# ezlpc.net
KiCad netlist of a schematic drawn in EAGLE
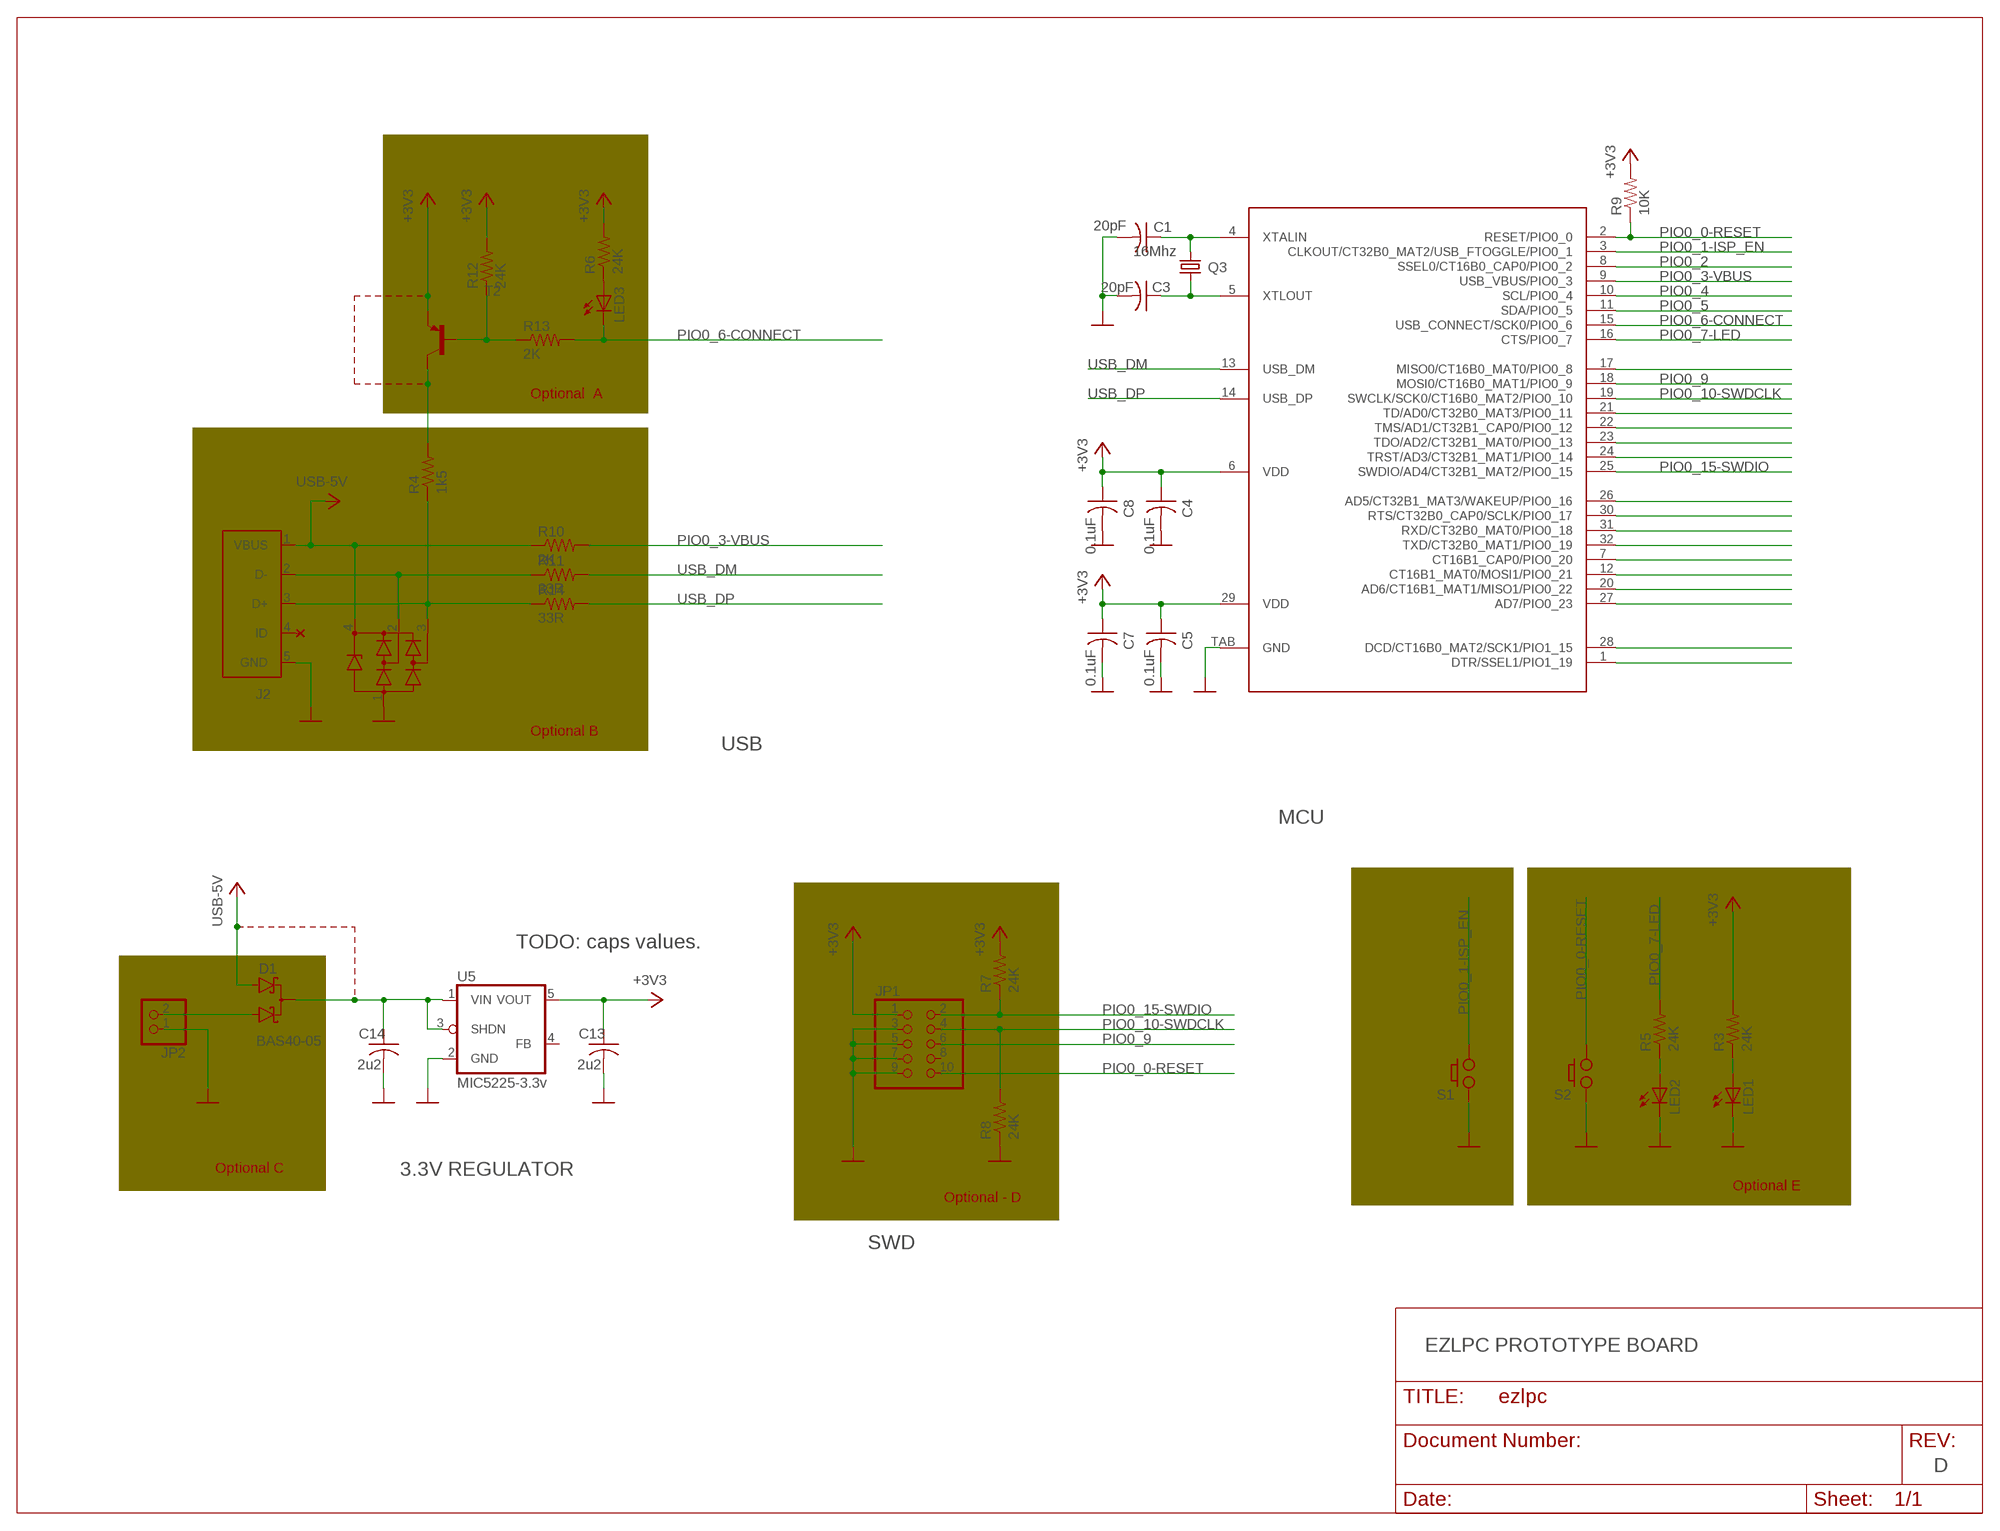
[diagram p0: schematic, sheet 1]

(export (version "E")
  (design (tool "Eeschema 10.0.6"))
  (components
    (comp (ref "C1")
      (value "20pF")
      (footprint "eagle-import:C0603")
      (libsource (lib "eagle-import") (part "CAP-C0603"))
    )
    (comp (ref "C3")
      (value "20pF")
      (footprint "eagle-import:C0603")
      (libsource (lib "eagle-import") (part "CAP-C0603"))
    )
    (comp (ref "C4")
      (value "0.1uF")
      (footprint "eagle-import:C0603")
      (libsource (lib "eagle-import") (part "CAP-C0603"))
    )
    (comp (ref "C5")
      (value "0.1uF")
      (footprint "eagle-import:C0603")
      (libsource (lib "eagle-import") (part "CAP-C0603"))
    )
    (comp (ref "C7")
      (value "0.1uF")
      (footprint "eagle-import:C0603")
      (libsource (lib "eagle-import") (part "CAP-C0603"))
    )
    (comp (ref "C8")
      (value "0.1uF")
      (footprint "eagle-import:C0603")
      (libsource (lib "eagle-import") (part "CAP-C0603"))
    )
    (comp (ref "C13")
      (value "2u2")
      (footprint "eagle-import:C0603")
      (libsource (lib "eagle-import") (part "CAP-C0603"))
    )
    (comp (ref "C14")
      (value "2u2")
      (footprint "eagle-import:C0603")
      (libsource (lib "eagle-import") (part "CAP-C0603"))
    )
    (comp (ref "D1")
      (value "BAS40-05")
      (footprint "eagle-import:SOT23")
      (libsource (lib "eagle-import") (part "BAS40-05"))
    )
    (comp (ref "J2")
      (value "USB")
      (footprint "eagle-import:USB-MICRO-ZX62RD-AB-5P8")
      (libsource (lib "eagle-import") (part "USB"))
    )
    (comp (ref "JP1")
      (value "SWD-HEADER")
      (footprint "eagle-import:SWD-HEADER")
      (libsource (lib "eagle-import") (part "SWD-HEADER"))
    )
    (comp (ref "JP2")
      (value "PINHD-1X2")
      (footprint "eagle-import:1X02")
      (libsource (lib "eagle-import") (part "PINHD-1X2"))
    )
    (comp (ref "LED1")
      (value "LEDCHIP-LED0603")
      (footprint "eagle-import:CHIP-LED0603")
      (libsource (lib "eagle-import") (part "LEDCHIP-LED0603"))
    )
    (comp (ref "LED2")
      (value "LEDCHIP-LED0603")
      (footprint "eagle-import:CHIP-LED0603")
      (libsource (lib "eagle-import") (part "LEDCHIP-LED0603"))
    )
    (comp (ref "LED3")
      (value "LEDCHIP-LED0603")
      (footprint "eagle-import:CHIP-LED0603")
      (libsource (lib "eagle-import") (part "LEDCHIP-LED0603"))
    )
    (comp (ref "Q3")
      (value "16Mhz")
      (footprint "eagle-import:CRYSTAL-CTS406")
      (libsource (lib "eagle-import") (part "CRYSTALCTS406"))
    )
    (comp (ref "R3")
      (value "24K")
      (footprint "eagle-import:R0402")
      (libsource (lib "eagle-import") (part "R-US_R0402"))
    )
    (comp (ref "R4")
      (value "1k5")
      (footprint "eagle-import:R0402")
      (libsource (lib "eagle-import") (part "R-US_R0402"))
    )
    (comp (ref "R5")
      (value "24K")
      (footprint "eagle-import:R0402")
      (libsource (lib "eagle-import") (part "R-US_R0402"))
    )
    (comp (ref "R6")
      (value "24K")
      (footprint "eagle-import:R0402")
      (libsource (lib "eagle-import") (part "R-US_R0402"))
    )
    (comp (ref "R7")
      (value "24K")
      (footprint "eagle-import:R0402")
      (libsource (lib "eagle-import") (part "R-US_R0402"))
    )
    (comp (ref "R8")
      (value "24K")
      (footprint "eagle-import:R0402")
      (libsource (lib "eagle-import") (part "R-US_R0402"))
    )
    (comp (ref "R9")
      (value "10K")
      (footprint "eagle-import:R0402")
      (libsource (lib "eagle-import") (part "R-US_R0402"))
    )
    (comp (ref "R10")
      (value "2K")
      (footprint "eagle-import:R0402")
      (libsource (lib "eagle-import") (part "R-US_R0402"))
    )
    (comp (ref "R11")
      (value "33R")
      (footprint "eagle-import:R0402")
      (libsource (lib "eagle-import") (part "R-US_R0402"))
    )
    (comp (ref "R12")
      (value "24K")
      (footprint "eagle-import:R0402")
      (libsource (lib "eagle-import") (part "R-US_R0402"))
    )
    (comp (ref "R13")
      (value "2K")
      (footprint "eagle-import:R0402")
      (libsource (lib "eagle-import") (part "R-US_R0402"))
    )
    (comp (ref "R14")
      (value "33R")
      (footprint "eagle-import:R0402")
      (libsource (lib "eagle-import") (part "R-US_R0402"))
    )
    (comp (ref "S1")
      (value "PUSH_BUTTON")
      (footprint "eagle-import:PUSH_BUTTON")
      (libsource (lib "eagle-import") (part "PUSH_BUTTON"))
    )
    (comp (ref "S2")
      (value "PUSH_BUTTON")
      (footprint "eagle-import:PUSH_BUTTON")
      (libsource (lib "eagle-import") (part "PUSH_BUTTON"))
    )
    (comp (ref "T2")
      (value "BC857B-PNP-SOT23-BEC")
      (footprint "eagle-import:SOT23-BEC")
      (libsource (lib "eagle-import") (part "-PNP-SOT23-BECBC857B"))
    )
    (comp (ref "U$5")
      (value "PRTR5VOU2X")
      (footprint "eagle-import:SOT143B")
      (libsource (lib "eagle-import") (part "PRTR5VOU2X"))
    )
    (comp (ref "U4")
      (value "LPC11U35FHN33/501")
      (footprint "eagle-import:HVQFN33-5MM")
      (libsource (lib "eagle-import") (part "LPC11U35FHN33/501"))
    )
    (comp (ref "U5")
      (value "MIC5225-3.3v")
      (footprint "eagle-import:SOT25")
      (libsource (lib "eagle-import") (part "TC1015"))
    )
  )
  (nets
    (net (code "1") (name "+3V3") (class "Default")
      (node (ref "C13") (pin "1") (pinfunction "1_1") (pintype "passive"))
      (node (ref "C4") (pin "1") (pinfunction "1_1") (pintype "passive"))
      (node (ref "C5") (pin "1") (pinfunction "1_1") (pintype "passive"))
      (node (ref "C7") (pin "1") (pinfunction "1_1") (pintype "passive"))
      (node (ref "C8") (pin "1") (pinfunction "1_1") (pintype "passive"))
      (node (ref "JP1") (pin "1") (pinfunction "1_1") (pintype "passive"))
      (node (ref "R12") (pin "2") (pinfunction "2_2") (pintype "passive"))
      (node (ref "R3") (pin "2") (pinfunction "2_2") (pintype "passive"))
      (node (ref "R6") (pin "2") (pinfunction "2_2") (pintype "passive"))
      (node (ref "R7") (pin "2") (pinfunction "2_2") (pintype "passive"))
      (node (ref "R9") (pin "2") (pinfunction "2_2") (pintype "passive"))
      (node (ref "T2") (pin "E") (pinfunction "E_E") (pintype "passive"))
      (node (ref "U4") (pin "29") (pinfunction "VDD_29") (pintype "bidirectional"))
      (node (ref "U4") (pin "6") (pinfunction "VDD_6") (pintype "bidirectional"))
      (node (ref "U5") (pin "5") (pinfunction "VOUT_5") (pintype "power_in"))
    )
    (net (code "2") (name "/PIO0_0-RESET") (class "Default")
      (node (ref "JP1") (pin "10") (pinfunction "10_10") (pintype "passive"))
      (node (ref "R9") (pin "1") (pinfunction "1_1") (pintype "passive"))
      (node (ref "S2") (pin "B2") (pinfunction "2_B2") (pintype "passive"))
      (node (ref "U4") (pin "2") (pinfunction "RESET/PIO0_0_2") (pintype "bidirectional"))
    )
    (net (code "3") (name "/PIO0_1-ISP_EN") (class "Default")
      (node (ref "S1") (pin "B2") (pinfunction "2_B2") (pintype "passive"))
      (node (ref "U4") (pin "3") (pinfunction "CLKOUT/CT32B0_MAT2/USB_FTOGGLE/PIO0_1_3") (pintype "bidirectional"))
    )
    (net (code "4") (name "/PIO0_2") (class "Default")
      (node (ref "U4") (pin "8") (pinfunction "SSEL0/CT16B0_CAP0/PIO0_2_8") (pintype "bidirectional"))
    )
    (net (code "5") (name "/PIO0_3-VBUS") (class "Default")
      (node (ref "R10") (pin "2") (pinfunction "2_2") (pintype "passive"))
      (node (ref "U4") (pin "9") (pinfunction "USB_VBUS/PIO0_3_9") (pintype "bidirectional"))
    )
    (net (code "6") (name "/PIO0_4") (class "Default")
      (node (ref "U4") (pin "10") (pinfunction "SCL/PIO0_4_10") (pintype "bidirectional"))
    )
    (net (code "7") (name "/PIO0_5") (class "Default")
      (node (ref "U4") (pin "11") (pinfunction "SDA/PIO0_5_11") (pintype "bidirectional"))
    )
    (net (code "8") (name "/PIO0_6-CONNECT") (class "Default")
      (node (ref "LED3") (pin "C") (pinfunction "C_C") (pintype "passive"))
      (node (ref "R13") (pin "2") (pinfunction "2_2") (pintype "passive"))
      (node (ref "U4") (pin "15") (pinfunction "USB_CONNECT/SCK0/PIO0_6_15") (pintype "bidirectional"))
    )
    (net (code "9") (name "/PIO0_7-LED") (class "Default")
      (node (ref "R5") (pin "2") (pinfunction "2_2") (pintype "passive"))
      (node (ref "U4") (pin "16") (pinfunction "CTS/PIO0_7_16") (pintype "bidirectional"))
    )
    (net (code "10") (name "/PIO0_9") (class "Default")
      (node (ref "JP1") (pin "6") (pinfunction "6_6") (pintype "passive"))
      (node (ref "U4") (pin "18") (pinfunction "MOSI0/CT16B0_MAT1/PIO0_9_18") (pintype "bidirectional"))
    )
    (net (code "11") (name "/PIO0_10-SWDCLK") (class "Default")
      (node (ref "JP1") (pin "4") (pinfunction "4_4") (pintype "passive"))
      (node (ref "R8") (pin "2") (pinfunction "2_2") (pintype "passive"))
      (node (ref "U4") (pin "19") (pinfunction "SWCLK/SCK0/CT16B0_MAT2/PIO0_10_19") (pintype "bidirectional"))
    )
    (net (code "12") (name "/PIO0_15-SWDIO") (class "Default")
      (node (ref "JP1") (pin "2") (pinfunction "2_2") (pintype "passive"))
      (node (ref "R7") (pin "1") (pinfunction "1_1") (pintype "passive"))
      (node (ref "U4") (pin "25") (pinfunction "SWDIO/AD4/CT32B1_MAT2/PIO0_15_25") (pintype "bidirectional"))
    )
    (net (code "13") (name "/USB_DM") (class "Default")
      (node (ref "R11") (pin "2") (pinfunction "2_2") (pintype "passive"))
      (node (ref "U4") (pin "13") (pinfunction "USB_DM_13") (pintype "bidirectional"))
    )
    (net (code "14") (name "/USB_DP") (class "Default")
      (node (ref "R14") (pin "2") (pinfunction "2_2") (pintype "passive"))
      (node (ref "U4") (pin "14") (pinfunction "USB_DP_14") (pintype "bidirectional"))
    )
    (net (code "15") (name "GND") (class "Default")
      (node (ref "C1") (pin "2") (pinfunction "2_2") (pintype "passive"))
      (node (ref "C13") (pin "2") (pinfunction "2_2") (pintype "passive"))
      (node (ref "C14") (pin "2") (pinfunction "2_2") (pintype "passive"))
      (node (ref "C3") (pin "2") (pinfunction "2_2") (pintype "passive"))
      (node (ref "C4") (pin "2") (pinfunction "2_2") (pintype "passive"))
      (node (ref "C5") (pin "2") (pinfunction "2_2") (pintype "passive"))
      (node (ref "C7") (pin "2") (pinfunction "2_2") (pintype "passive"))
      (node (ref "C8") (pin "2") (pinfunction "2_2") (pintype "passive"))
      (node (ref "J2") (pin "5") (pinfunction "GND_5") (pintype "bidirectional"))
      (node (ref "JP1") (pin "3") (pinfunction "3_3") (pintype "passive"))
      (node (ref "JP1") (pin "5") (pinfunction "5_5") (pintype "passive"))
      (node (ref "JP1") (pin "7") (pinfunction "7_7") (pintype "passive"))
      (node (ref "JP1") (pin "9") (pinfunction "9_9") (pintype "passive"))
      (node (ref "JP2") (pin "1") (pinfunction "1_1") (pintype "passive"))
      (node (ref "LED1") (pin "C") (pinfunction "C_C") (pintype "passive"))
      (node (ref "LED2") (pin "C") (pinfunction "C_C") (pintype "passive"))
      (node (ref "R8") (pin "1") (pinfunction "1_1") (pintype "passive"))
      (node (ref "S1") (pin "A1") (pinfunction "1_A1") (pintype "passive"))
      (node (ref "S2") (pin "A1") (pinfunction "1_A1") (pintype "passive"))
      (node (ref "U$5") (pin "1") (pinfunction "GND_1") (pintype "passive"))
      (node (ref "U4") (pin "TAB") (pinfunction "GND_TAB") (pintype "bidirectional"))
      (node (ref "U5") (pin "2") (pinfunction "GND_2") (pintype "power_in"))
    )
    (net (code "16") (name "Net-(D1-A1)") (class "Default")
      (node (ref "D1") (pin "1") (pinfunction "A1_1") (pintype "passive"))
      (node (ref "JP2") (pin "2") (pinfunction "2_2") (pintype "passive"))
    )
    (net (code "17") (name "Net-(D1-C)") (class "Default")
      (node (ref "C14") (pin "1") (pinfunction "1_1") (pintype "passive"))
      (node (ref "D1") (pin "3") (pinfunction "C_3") (pintype "passive"))
      (node (ref "U5") (pin "1") (pinfunction "VIN_1") (pintype "power_in"))
      (node (ref "U5") (pin "3") (pinfunction "SHDN_3") (pintype "input"))
    )
    (net (code "18") (name "Net-(J2-D+)") (class "Default")
      (node (ref "J2") (pin "2") (pinfunction "D-_2") (pintype "bidirectional"))
      (node (ref "J2") (pin "3") (pinfunction "D+_3") (pintype "bidirectional"))
      (node (ref "R11") (pin "1") (pinfunction "1_1") (pintype "passive"))
      (node (ref "R14") (pin "1") (pinfunction "1_1") (pintype "passive"))
      (node (ref "R4") (pin "1") (pinfunction "1_1") (pintype "passive"))
      (node (ref "U$5") (pin "2") (pinfunction "IO1_2") (pintype "passive"))
      (node (ref "U$5") (pin "3") (pinfunction "IO2_3") (pintype "passive"))
    )
    (net (code "19") (name "Net-(LED1-PadA)") (class "Default")
      (node (ref "LED1") (pin "A") (pinfunction "A_A") (pintype "passive"))
      (node (ref "R3") (pin "1") (pinfunction "1_1") (pintype "passive"))
    )
    (net (code "20") (name "Net-(LED2-PadA)") (class "Default")
      (node (ref "LED2") (pin "A") (pinfunction "A_A") (pintype "passive"))
      (node (ref "R5") (pin "1") (pinfunction "1_1") (pintype "passive"))
    )
    (net (code "21") (name "Net-(LED3-PadA)") (class "Default")
      (node (ref "LED3") (pin "A") (pinfunction "A_A") (pintype "passive"))
      (node (ref "R6") (pin "1") (pinfunction "1_1") (pintype "passive"))
    )
    (net (code "22") (name "Net-(Q3-2)") (class "Default")
      (node (ref "C3") (pin "1") (pinfunction "1_1") (pintype "passive"))
      (node (ref "Q3") (pin "3") (pinfunction "2_3") (pintype "passive"))
      (node (ref "U4") (pin "5") (pinfunction "XTLOUT_5") (pintype "bidirectional"))
    )
    (net (code "23") (name "Net-(R4-Pad2)") (class "Default")
      (node (ref "R4") (pin "2") (pinfunction "2_2") (pintype "passive"))
      (node (ref "T2") (pin "C") (pinfunction "C_C") (pintype "passive"))
    )
    (net (code "24") (name "Net-(R12-Pad1)") (class "Default")
      (node (ref "R12") (pin "1") (pinfunction "1_1") (pintype "passive"))
      (node (ref "R13") (pin "1") (pinfunction "1_1") (pintype "passive"))
      (node (ref "T2") (pin "B") (pinfunction "B_B") (pintype "passive"))
    )
    (net (code "25") (name "Net-(U4-XTALIN)") (class "Default")
      (node (ref "C1") (pin "1") (pinfunction "1_1") (pintype "passive"))
      (node (ref "Q3") (pin "1") (pinfunction "1_1") (pintype "passive"))
      (node (ref "U4") (pin "4") (pinfunction "XTALIN_4") (pintype "bidirectional"))
    )
    (net (code "26") (name "USB-5V") (class "Default")
      (node (ref "D1") (pin "2") (pinfunction "A2_2") (pintype "passive"))
      (node (ref "J2") (pin "1") (pinfunction "VBUS_1") (pintype "bidirectional"))
      (node (ref "R10") (pin "1") (pinfunction "1_1") (pintype "passive"))
      (node (ref "U$5") (pin "4") (pinfunction "VCC_4") (pintype "passive"))
    )
    (net (code "27") (name "unconnected-(J2-ID-Pad4)") (class "Default")
      (node (ref "J2") (pin "4") (pinfunction "ID_4") (pintype "bidirectional"))
    )
    (net (code "28") (name "unconnected-(JP1-Pad8)") (class "Default")
      (node (ref "JP1") (pin "8") (pinfunction "8_8") (pintype "passive"))
    )
    (net (code "29") (name "unconnected-(U4-AD5{slash}CT32B1_MAT3{slash}WAKEUP{slash}PIO0_16-Pad26)") (class "Default")
      (node (ref "U4") (pin "26") (pinfunction "AD5/CT32B1_MAT3/WAKEUP/PIO0_16_26") (pintype "bidirectional"))
    )
    (net (code "30") (name "unconnected-(U4-AD6{slash}CT16B1_MAT1{slash}MISO1{slash}PIO0_22-Pad20)") (class "Default")
      (node (ref "U4") (pin "20") (pinfunction "AD6/CT16B1_MAT1/MISO1/PIO0_22_20") (pintype "bidirectional"))
    )
    (net (code "31") (name "unconnected-(U4-AD7{slash}PIO0_23-Pad27)") (class "Default")
      (node (ref "U4") (pin "27") (pinfunction "AD7/PIO0_23_27") (pintype "bidirectional"))
    )
    (net (code "32") (name "unconnected-(U4-CT16B1_CAP0{slash}PIO0_20-Pad7)") (class "Default")
      (node (ref "U4") (pin "7") (pinfunction "CT16B1_CAP0/PIO0_20_7") (pintype "bidirectional"))
    )
    (net (code "33") (name "unconnected-(U4-CT16B1_MAT0{slash}MOSI1{slash}PIO0_21-Pad12)") (class "Default")
      (node (ref "U4") (pin "12") (pinfunction "CT16B1_MAT0/MOSI1/PIO0_21_12") (pintype "bidirectional"))
    )
    (net (code "34") (name "unconnected-(U4-DCD{slash}CT16B0_MAT2{slash}SCK1{slash}PIO1_15-Pad28)") (class "Default")
      (node (ref "U4") (pin "28") (pinfunction "DCD/CT16B0_MAT2/SCK1/PIO1_15_28") (pintype "bidirectional"))
    )
    (net (code "35") (name "unconnected-(U4-DTR{slash}SSEL1{slash}PIO1_19-Pad1)") (class "Default")
      (node (ref "U4") (pin "1") (pinfunction "DTR/SSEL1/PIO1_19_1") (pintype "bidirectional"))
    )
    (net (code "36") (name "unconnected-(U4-MISO0{slash}CT16B0_MAT0{slash}PIO0_8-Pad17)") (class "Default")
      (node (ref "U4") (pin "17") (pinfunction "MISO0/CT16B0_MAT0/PIO0_8_17") (pintype "bidirectional"))
    )
    (net (code "37") (name "unconnected-(U4-RTS{slash}CT32B0_CAP0{slash}SCLK{slash}PIO0_17-Pad30)") (class "Default")
      (node (ref "U4") (pin "30") (pinfunction "RTS/CT32B0_CAP0/SCLK/PIO0_17_30") (pintype "bidirectional"))
    )
    (net (code "38") (name "unconnected-(U4-RXD{slash}CT32B0_MAT0{slash}PIO0_18-Pad31)") (class "Default")
      (node (ref "U4") (pin "31") (pinfunction "RXD/CT32B0_MAT0/PIO0_18_31") (pintype "bidirectional"))
    )
    (net (code "39") (name "unconnected-(U4-TDO{slash}AD2{slash}CT32B1_MAT0{slash}PIO0_13-Pad23)") (class "Default")
      (node (ref "U4") (pin "23") (pinfunction "TDO/AD2/CT32B1_MAT0/PIO0_13_23") (pintype "bidirectional"))
    )
    (net (code "40") (name "unconnected-(U4-TD{slash}AD0{slash}CT32B0_MAT3{slash}PIO0_11-Pad21)") (class "Default")
      (node (ref "U4") (pin "21") (pinfunction "TD/AD0/CT32B0_MAT3/PIO0_11_21") (pintype "bidirectional"))
    )
    (net (code "41") (name "unconnected-(U4-TMS{slash}AD1{slash}CT32B1_CAP0{slash}PIO0_12-Pad22)") (class "Default")
      (node (ref "U4") (pin "22") (pinfunction "TMS/AD1/CT32B1_CAP0/PIO0_12_22") (pintype "bidirectional"))
    )
    (net (code "42") (name "unconnected-(U4-TRST{slash}AD3{slash}CT32B1_MAT1{slash}PIO0_14-Pad24)") (class "Default")
      (node (ref "U4") (pin "24") (pinfunction "TRST/AD3/CT32B1_MAT1/PIO0_14_24") (pintype "bidirectional"))
    )
    (net (code "43") (name "unconnected-(U4-TXD{slash}CT32B0_MAT1{slash}PIO0_19-Pad32)") (class "Default")
      (node (ref "U4") (pin "32") (pinfunction "TXD/CT32B0_MAT1/PIO0_19_32") (pintype "bidirectional"))
    )
    (net (code "44") (name "unconnected-(U5-FB-Pad4)") (class "Default")
      (node (ref "U5") (pin "4") (pinfunction "FB_4") (pintype "input"))
    )
  )
)
